# POWER_INPUT.net
KiCad netlist of a schematic drawn in Altium Designer
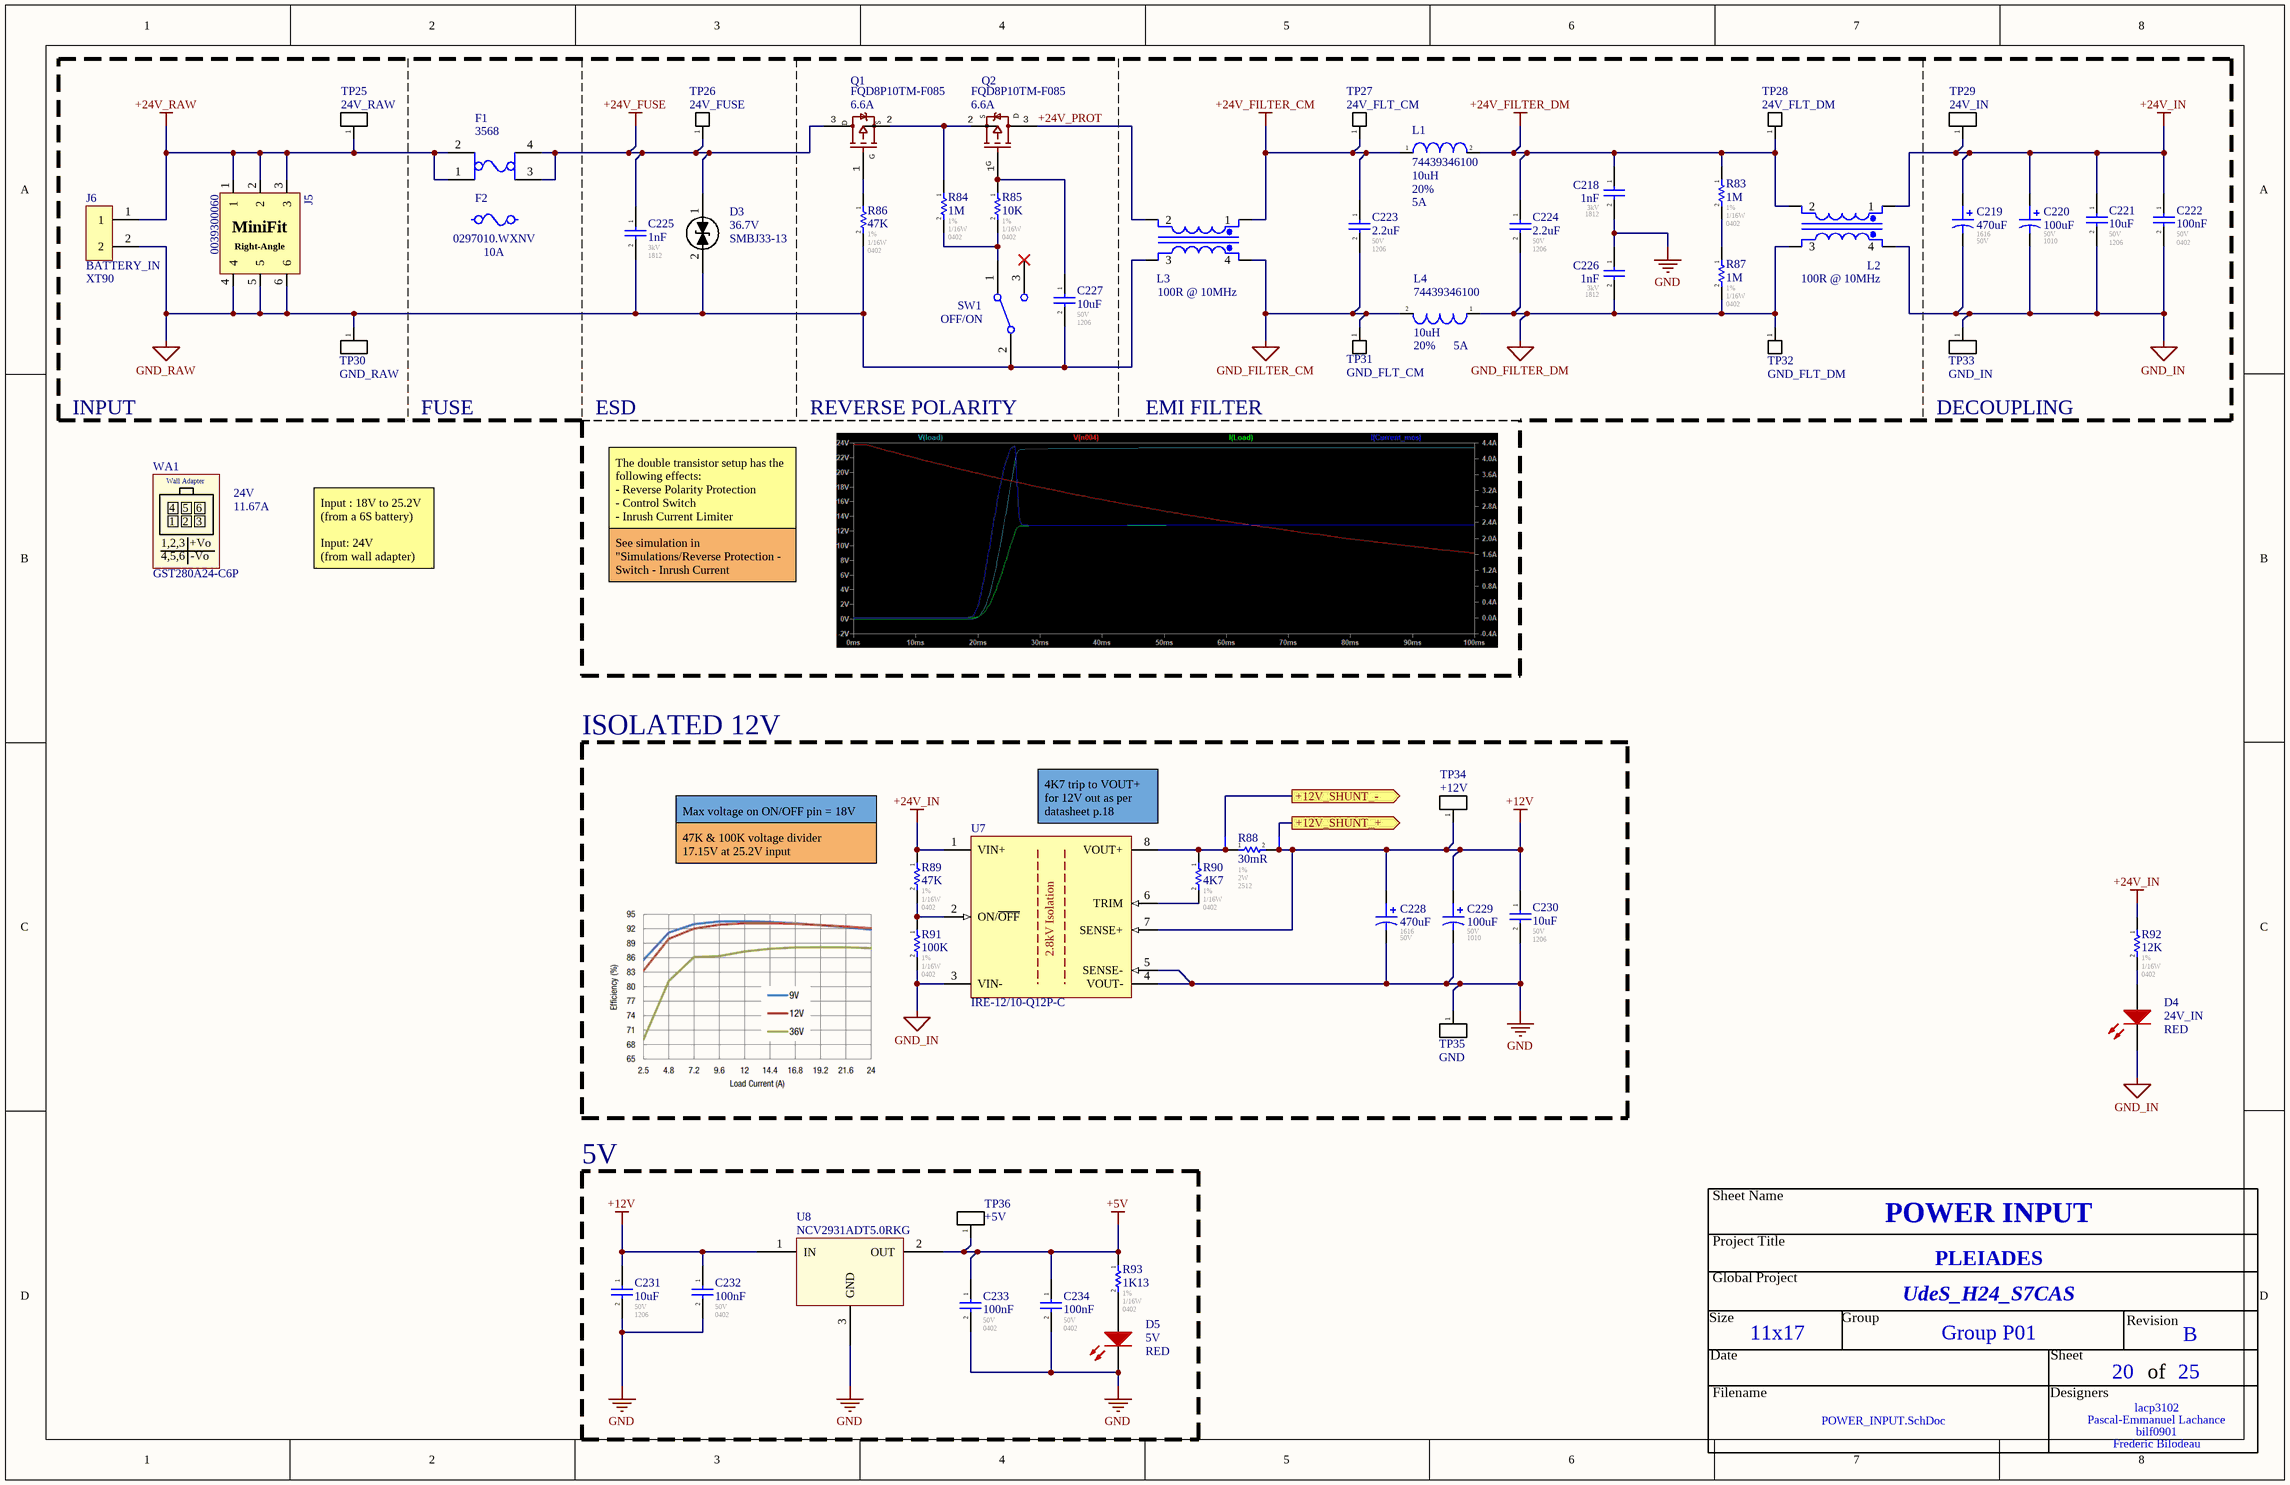
[diagram p0: POWER_INPUT.SchDoc]

(export (version "E")
  (design (tool "Eeschema 10.0.6"))
  (components
    (comp (ref "C218")
      (value "1nF")
      (footprint "1812")
      (description "C1812C102KHRACAUTO\r\n0402 470pF 10% X7R Ceramic Capacitor")
      (fields
        (field (name "MFR") "KEMET")
        (field (name "PART#") "C1812C102KHRACAUTO")
        (field (name "VOLTAGE - RATED") "3kV")
      )
      (libsource (lib "Symbols") (part "CAP_CER"))
    )
    (comp (ref "C219")
      (value "470uF")
      (footprint "CAP_ALU_1616_vishay")
      (description "CAP - ALU 470uF 20% 50V - 1616")
      (fields
        (field (name "MFG") "Vishay Dale")
        (field (name "MFG PART NUMBER") "MAL214699108E3")
        (field (name "VOLTAGE") "50V")
        (field (name "PACKAGE") "1616")
        (field (name "CREATEDBY") "Jonathan Bouchard")
      )
      (libsource (lib "S7CAS_LIB2023") (part "CAP_ALU_MAL214699108E3"))
    )
    (comp (ref "C220")
      (value "100uF")
      (footprint "CAP_ALU_1010_vishay")
      (description "CAP - ALU 100uF 20% 50V - 1010")
      (fields
        (field (name "MFG") "Vishay Dale")
        (field (name "MFG PART NUMBER") "MAL215099101E3")
        (field (name "VOLTAGE") "50V")
        (field (name "PACKAGE") "1010")
        (field (name "CREATEDBY") "Jonathan Bouchard")
      )
      (libsource (lib "S7CAS_LIB2023") (part "CAP_ALU_MAL215099101E3"))
    )
    (comp (ref "C221")
      (value "10uF")
      (footprint "1206")
      (description "GRT31CR61H106KE01L\r\n1206 10uF 10% X5R Ceramic Capacitor")
      (fields
        (field (name "MFR") "Murata")
        (field (name "VOLTAGE - RATED") "50V")
        (field (name "TOLERANCE") "10%")
      )
      (libsource (lib "Symbols") (part "CAP_CER"))
    )
    (comp (ref "C222")
      (value "100nF")
      (footprint "0402")
      (description "GCM155R71H104KE02J\r\n0402 100nF 10% X7R Ceramic Capacitor")
      (fields
        (field (name "MFR") "Murata")
        (field (name "PART#") "GCM155R71H104KE02J")
        (field (name "VOLTAGE - RATED") "50V")
      )
      (libsource (lib "Symbols") (part "CAP_CER"))
    )
    (comp (ref "C223")
      (value "2.2uF")
      (footprint "1206")
      (description "GRT31CR71H225KE13L\r\n1206 2.2uF 10% X7R Ceramic Capacitor")
      (fields
        (field (name "MFR") "Murata")
        (field (name "PART#") "GRT31CR71H225KE13L")
        (field (name "VOLTAGE - RATED") "50V")
      )
      (libsource (lib "Symbols") (part "CAP_CER"))
    )
    (comp (ref "C224")
      (value "2.2uF")
      (footprint "1206")
      (description "GRT31CR71H225KE13L\r\n1206 2.2uF 10% X7R Ceramic Capacitor")
      (fields
        (field (name "MFR") "Murata")
        (field (name "PART#") "GRT31CR71H225KE13L")
        (field (name "VOLTAGE - RATED") "50V")
      )
      (libsource (lib "Symbols") (part "CAP_CER"))
    )
    (comp (ref "C225")
      (value "1nF")
      (footprint "1812")
      (description "C1812C102KHRACAUTO\r\n0402 470pF 10% X7R Ceramic Capacitor")
      (fields
        (field (name "MFR") "KEMET")
        (field (name "PART#") "C1812C102KHRACAUTO")
        (field (name "VOLTAGE - RATED") "3kV")
      )
      (libsource (lib "Symbols") (part "CAP_CER"))
    )
    (comp (ref "C226")
      (value "1nF")
      (footprint "1812")
      (description "C1812C102KHRACAUTO\r\n0402 470pF 10% X7R Ceramic Capacitor")
      (fields
        (field (name "MFR") "KEMET")
        (field (name "PART#") "C1812C102KHRACAUTO")
        (field (name "VOLTAGE - RATED") "3kV")
      )
      (libsource (lib "Symbols") (part "CAP_CER"))
    )
    (comp (ref "C227")
      (value "10uF")
      (footprint "1206")
      (description "GRT31CR61H106KE01L\r\n1206 10uF 10% X5R Ceramic Capacitor")
      (fields
        (field (name "MFR") "Murata")
        (field (name "VOLTAGE - RATED") "50V")
        (field (name "TOLERANCE") "10%")
      )
      (libsource (lib "Symbols") (part "CAP_CER"))
    )
    (comp (ref "C228")
      (value "470uF")
      (footprint "CAP_ALU_1616_vishay")
      (description "CAP - ALU 470uF 20% 50V - 1616")
      (fields
        (field (name "MFG") "Vishay Dale")
        (field (name "MFG PART NUMBER") "MAL214699108E3")
        (field (name "VOLTAGE") "50V")
        (field (name "PACKAGE") "1616")
        (field (name "CREATEDBY") "Jonathan Bouchard")
      )
      (libsource (lib "S7CAS_LIB2023") (part "CAP_ALU_MAL214699108E3"))
    )
    (comp (ref "C229")
      (value "100uF")
      (footprint "CAP_ALU_1010_vishay")
      (description "CAP - ALU 100uF 20% 50V - 1010")
      (fields
        (field (name "MFG") "Vishay Dale")
        (field (name "MFG PART NUMBER") "MAL215099101E3")
        (field (name "VOLTAGE") "50V")
        (field (name "PACKAGE") "1010")
        (field (name "CREATEDBY") "Jonathan Bouchard")
      )
      (libsource (lib "S7CAS_LIB2023") (part "CAP_ALU_MAL215099101E3"))
    )
    (comp (ref "C230")
      (value "10uF")
      (footprint "1206")
      (description "GRT31CR61H106KE01L\r\n1206 10uF 10% X5R Ceramic Capacitor")
      (fields
        (field (name "MFR") "Murata")
        (field (name "VOLTAGE - RATED") "50V")
        (field (name "TOLERANCE") "10%")
      )
      (libsource (lib "Symbols") (part "CAP_CER"))
    )
    (comp (ref "C231")
      (value "10uF")
      (footprint "1206")
      (description "GRT31CR61H106KE01L\r\n1206 10uF 10% X5R Ceramic Capacitor")
      (fields
        (field (name "MFR") "Murata")
        (field (name "VOLTAGE - RATED") "50V")
        (field (name "TOLERANCE") "10%")
      )
      (libsource (lib "Symbols") (part "CAP_CER"))
    )
    (comp (ref "C232")
      (value "100nF")
      (footprint "0402")
      (description "GCM155R71H104KE02J\r\n0402 100nF 10% X7R Ceramic Capacitor")
      (fields
        (field (name "MFR") "Murata")
        (field (name "PART#") "GCM155R71H104KE02J")
        (field (name "VOLTAGE - RATED") "50V")
      )
      (libsource (lib "Symbols") (part "CAP_CER"))
    )
    (comp (ref "C233")
      (value "100nF")
      (footprint "0402")
      (description "GCM155R71H104KE02J\r\n0402 100nF 10% X7R Ceramic Capacitor")
      (fields
        (field (name "MFR") "Murata")
        (field (name "PART#") "GCM155R71H104KE02J")
        (field (name "VOLTAGE - RATED") "50V")
      )
      (libsource (lib "Symbols") (part "CAP_CER"))
    )
    (comp (ref "C234")
      (value "100nF")
      (footprint "0402")
      (description "GCM155R71H104KE02J\r\n0402 100nF 10% X7R Ceramic Capacitor")
      (fields
        (field (name "MFR") "Murata")
        (field (name "PART#") "GCM155R71H104KE02J")
        (field (name "VOLTAGE - RATED") "50V")
      )
      (libsource (lib "Symbols") (part "CAP_CER"))
    )
    (comp (ref "D3")
      (value "SMBJ33-13")
      (footprint "DO214AA (SMB)")
      (description "53.3V Clamp 11.3A Ipp Tvs Diode Surface Mount SMB")
      (fields (field (name "MFR") "SMBJ33CAQ-13-F") (field (name "VOLTAGE - BREAKDOWN") "36.7V"))
      (libsource (lib "Symbols") (part "DIODE_TVS"))
    )
    (comp (ref "D4")
      (value "24V_IN")
      (footprint "LED_0603")
      (description "LED - 620nM RED 2mA - 0603")
      (fields
        (field (name "VOLTAGE") "1.8V")
        (field (name "MFG") "ROHM Semiconductor")
        (field (name "ALTIUM_VALUE") "RED")
        (field (name "CREATEDBY") "Jonathan Bouchard")
      )
      (libsource (lib "S7CAS_LIB2023") (part "LED_SML-311UTT86"))
    )
    (comp (ref "D5")
      (value "5V")
      (footprint "LED_0603")
      (description "LED - 620nM RED 2mA - 0603")
      (fields
        (field (name "VOLTAGE") "1.8V")
        (field (name "MFG") "ROHM Semiconductor")
        (field (name "ALTIUM_VALUE") "RED")
        (field (name "CREATEDBY") "Jonathan Bouchard")
      )
      (libsource (lib "S7CAS_LIB2023") (part "LED_SML-311UTT86"))
    )
    (comp (ref "F1")
      (value "3568")
      (footprint "3568")
      (description "FUSE HOLDER BLADE")
      (fields (field (name "MFR") "Keystone") (field (name "CREATED BY") "Pascal-Emmanuel Lachance"))
      (libsource (lib "CryptLib") (part "FUSE_HOLDER_3568"))
    )
    (comp (ref "F2")
      (value "0297010.WXNV")
      (footprint "0297010.WXNV")
      (description "FUSE AUTO 10A 32V BLADE MINI")
      (fields
        (field (name "MFR") "Littelfuse")
        (field (name "CURRENT - TRIP") "10A")
        (field (name "CREATED BY") "Pascal-Emmanuel Lachance")
      )
      (libsource (lib "CryptLib") (part "FUSE_0297010.WXNV"))
    )
    (comp (ref "J5")
      (value "0039300060")
      (footprint "CON_MINIFIT_0039300060")
      (description "CON - Mini-Fit Through Hole, Right Angle 6 position")
      (fields
        (field (name "CREATEDBY/DATE") "Joel Lemay 2018-06-21")
        (field (name "VERIFIEDBY") "Caroline Paulin - 10 sept 2018")
      )
      (libsource (lib "S7CAS_LIB2023") (part "CON_MINIFIT_0039300060"))
    )
    (comp (ref "J6")
      (value "BATTERY_IN")
      (footprint "XT90")
      (fields (field (name "TYPE") "XT90"))
      (libsource (lib "Connectors") (part "XT90"))
    )
    (comp (ref "L1")
      (value "74439346100")
      (footprint "74439346100")
      (description "Generic Inductor")
      (fields
        (field (name "INDUCTANCE") "10uH")
        (field (name "TOLERANCE") "20%")
        (field (name "CURRENT RATING") "5A")
      )
      (libsource (lib "Symbols") (part "INDUCTOR"))
    )
    (comp (ref "L2")
      (value "100R @ 10MHz")
      (footprint "IND_PLT10HH101150PNL")
      (fields
        (field (name "Comment") "PLT10HH101150PNL")
        (field (name "CREATEDBY/DATE") "Tommy Rossginol - 2019/04/09")
        (field (name "VERIFIEDBY") "Caroline Paulin - 10-04-2019")
      )
      (libsource (lib "S7CAS_LIB2023") (part "IND_PLT10HH101150PNL"))
    )
    (comp (ref "L3")
      (value "100R @ 10MHz")
      (footprint "IND_PLT10HH101150PNL")
      (fields
        (field (name "Comment") "PLT10HH101150PNL")
        (field (name "CREATEDBY/DATE") "Tommy Rossginol - 2019/04/09")
        (field (name "VERIFIEDBY") "Caroline Paulin - 10-04-2019")
      )
      (libsource (lib "S7CAS_LIB2023") (part "IND_PLT10HH101150PNL"))
    )
    (comp (ref "L4")
      (value "74439346100")
      (footprint "74439346100")
      (description "Generic Inductor")
      (fields
        (field (name "INDUCTANCE") "10uH")
        (field (name "TOLERANCE") "20%")
        (field (name "CURRENT RATING") "5A")
      )
      (libsource (lib "Symbols") (part "INDUCTOR"))
    )
    (comp (ref "NT38")
      (value "Net Tie")
      (footprint "NETTIE_5")
      (libsource (lib "Symbols") (part "NET_TIE_SMALL"))
    )
    (comp (ref "NT39")
      (value "Net Tie")
      (footprint "NETTIE_5")
      (libsource (lib "Symbols") (part "NET_TIE_SMALL"))
    )
    (comp (ref "Q1")
      (value "FQD8P10TM-F085")
      (footprint "DPAK")
      (description "P-Channel 100 V 6.6A (Tc) 2.5W (Ta), 44W (Tc) Surface Mount TO-252AA")
      (fields (field (name "MFR") "onsemi") (field (name "CURRENT") "6.6A"))
      (libsource (lib "Symbols") (part "P_CHANNEL"))
    )
    (comp (ref "Q2")
      (value "FQD8P10TM-F085")
      (footprint "DPAK")
      (description "P-Channel 100 V 6.6A (Tc) 2.5W (Ta), 44W (Tc) Surface Mount TO-252AA")
      (fields (field (name "MFR") "onsemi") (field (name "CURRENT") "6.6A"))
      (libsource (lib "Symbols") (part "P_CHANNEL"))
    )
    (comp (ref "R83")
      (value "1M")
      (footprint "RES_0402")
      (description "1M 0402 1% 1/16W Resistor")
      (fields
        (field (name "TOLERANCE") "1%")
        (field (name "POWER") "1/16W")
        (field (name "PACKAGE / CASE") "0402")
      )
      (libsource (lib "Symbols") (part "RESISTOR"))
    )
    (comp (ref "R84")
      (value "1M")
      (footprint "RES_0402")
      (description "1M 0402 1% 1/16W Resistor")
      (fields
        (field (name "TOLERANCE") "1%")
        (field (name "POWER") "1/16W")
        (field (name "PACKAGE / CASE") "0402")
      )
      (libsource (lib "Symbols") (part "RESISTOR"))
    )
    (comp (ref "R85")
      (value "10K")
      (footprint "RES_0402")
      (fields
        (field (name "TOLERANCE") "1%")
        (field (name "POWER") "1/16W")
        (field (name "PACKAGE / CASE") "0402")
      )
      (libsource (lib "Symbols") (part "RESISTOR"))
    )
    (comp (ref "R86")
      (value "47K")
      (footprint "RES_0402")
      (fields
        (field (name "TOLERANCE") "1%")
        (field (name "POWER") "1/16W")
        (field (name "PACKAGE / CASE") "0402")
      )
      (libsource (lib "Symbols") (part "RESISTOR"))
    )
    (comp (ref "R87")
      (value "1M")
      (footprint "RES_0402")
      (description "1M 0402 1% 1/16W Resistor")
      (fields
        (field (name "TOLERANCE") "1%")
        (field (name "POWER") "1/16W")
        (field (name "PACKAGE / CASE") "0402")
      )
      (libsource (lib "Symbols") (part "RESISTOR"))
    )
    (comp (ref "R88")
      (value "30mR")
      (footprint "RES_2512")
      (description "CSRN2512FK30L0")
      (fields
        (field (name "TOLERANCE") "1%")
        (field (name "POWER") "2W")
        (field (name "PACKAGE / CASE") "2512")
      )
      (libsource (lib "Symbols") (part "RESISTOR"))
    )
    (comp (ref "R89")
      (value "47K")
      (footprint "RES_0402")
      (fields
        (field (name "TOLERANCE") "1%")
        (field (name "POWER") "1/16W")
        (field (name "PACKAGE / CASE") "0402")
      )
      (libsource (lib "Symbols") (part "RESISTOR"))
    )
    (comp (ref "R90")
      (value "4K7")
      (footprint "RES_0402")
      (fields
        (field (name "TOLERANCE") "1%")
        (field (name "POWER") "1/16W")
        (field (name "PACKAGE / CASE") "0402")
      )
      (libsource (lib "Symbols") (part "RESISTOR"))
    )
    (comp (ref "R91")
      (value "100K")
      (footprint "RES_0402")
      (fields
        (field (name "TOLERANCE") "1%")
        (field (name "POWER") "1/16W")
        (field (name "PACKAGE / CASE") "0402")
      )
      (libsource (lib "Symbols") (part "RESISTOR"))
    )
    (comp (ref "R92")
      (value "12K")
      (footprint "RES_0402")
      (fields
        (field (name "TOLERANCE") "1%")
        (field (name "POWER") "1/16W")
        (field (name "PACKAGE / CASE") "0402")
      )
      (libsource (lib "Symbols") (part "RESISTOR"))
    )
    (comp (ref "R93")
      (value "1K13")
      (footprint "RES_0402")
      (fields
        (field (name "TOLERANCE") "1%")
        (field (name "POWER") "1/16W")
        (field (name "PACKAGE / CASE") "0402")
      )
      (libsource (lib "Symbols") (part "RESISTOR"))
    )
    (comp (ref "SW1")
      (value "OFF/ON")
      (footprint "1101M2S3CQE2")
      (description "1103M2S3CQE2\r\nSlide Switch SPDT Through Hole")
      (fields (field (name "MFR") "C&K"))
      (libsource (lib "Symbols") (part "SPDT_SWITCH"))
    )
    (comp (ref "TP25")
      (value "24V_RAW")
      (footprint "TP_HOLE")
      (description "Test Point")
      (libsource (lib "Symbols") (part "TESTPOINT"))
    )
    (comp (ref "TP26")
      (value "24V_FUSE")
      (footprint "TP_PAD")
      (description "Test Point")
      (libsource (lib "Symbols") (part "TESTPOINT_PAD"))
    )
    (comp (ref "TP27")
      (value "24V_FLT_CM")
      (footprint "TP_PAD")
      (description "Test Point")
      (libsource (lib "Symbols") (part "TESTPOINT_PAD"))
    )
    (comp (ref "TP28")
      (value "24V_FLT_DM")
      (footprint "TP_PAD")
      (description "Test Point")
      (libsource (lib "Symbols") (part "TESTPOINT_PAD"))
    )
    (comp (ref "TP29")
      (value "24V_IN")
      (footprint "TP_HOLE")
      (description "Test Point")
      (libsource (lib "Symbols") (part "TESTPOINT"))
    )
    (comp (ref "TP30")
      (value "GND_RAW")
      (footprint "TP_HOLE")
      (description "Test Point")
      (libsource (lib "Symbols") (part "TESTPOINT"))
    )
    (comp (ref "TP31")
      (value "GND_FLT_CM")
      (footprint "TP_PAD")
      (description "Test Point")
      (libsource (lib "Symbols") (part "TESTPOINT_PAD"))
    )
    (comp (ref "TP32")
      (value "GND_FLT_DM")
      (footprint "TP_PAD")
      (description "Test Point")
      (libsource (lib "Symbols") (part "TESTPOINT_PAD"))
    )
    (comp (ref "TP33")
      (value "GND_IN")
      (footprint "TP_HOLE")
      (description "Test Point")
      (libsource (lib "Symbols") (part "TESTPOINT"))
    )
    (comp (ref "TP34")
      (value "+12V")
      (footprint "TP_HOLE")
      (description "Test Point")
      (libsource (lib "Symbols") (part "TESTPOINT"))
    )
    (comp (ref "TP35")
      (value "GND")
      (footprint "TP_HOLE")
      (description "Test Point")
      (libsource (lib "Symbols") (part "TESTPOINT"))
    )
    (comp (ref "TP36")
      (value "+5V")
      (footprint "TP_HOLE")
      (description "Test Point")
      (libsource (lib "Symbols") (part "TESTPOINT"))
    )
    (comp (ref "U7")
      (value "IRE-12/10-Q12P-C")
      (footprint "IRE-Q12")
      (description "Isolated DC/DC Converters - Through Hole 9V-36VIN 24VOUT 120W")
      (fields (field (name "MFR") "Murata"))
      (libsource (lib "Misc") (part "IRE-24/5-Q12P-C"))
    )
    (comp (ref "U8")
      (value "NCV2931ADT5.0RKG")
      (footprint "DPAK")
      (libsource (lib "Misc") (part "NCV2931ADT5.0RKG"))
    )
    (comp (ref "WA1")
      (value "GST280A24-C6P")
      (footprint "Model Name")
      (description "UND - AC/DC DESKTOP ADAPTER 24V 280W - MEC")
      (fields
        (field (name "TOLERANCE") "±3%")
        (field (name "CURRENT RATING") "11.67A")
        (field (name "ALTIUM_VALUE") "24V")
        (field (name "CREATEDBY/DATE") "Caroline Paulin - 5 avril 2019")
        (field (name "VERIFIEDBY") "Nicolas V. (2019-07-05)")
      )
      (libsource (lib "S7CAS_LIB2023") (part "UND_GST280A24-C6P"))
    )
  )
  (nets
    (net (code "1") (name "+5V") (class "Default")
      (node (ref "C233") (pin "1") (pinfunction "1_1") (pintype "passive"))
      (node (ref "C234") (pin "1") (pinfunction "1_1") (pintype "passive"))
      (node (ref "R93") (pin "1") (pinfunction "1_1") (pintype "passive"))
      (node (ref "TP36") (pin "1") (pinfunction "A_1") (pintype "passive"))
      (node (ref "U8") (pin "2") (pinfunction "OUT_2") (pintype "passive"))
    )
    (net (code "2") (name "+12V") (class "Default")
      (node (ref "C228") (pin "1") (pinfunction "1_1") (pintype "passive"))
      (node (ref "C229") (pin "1") (pinfunction "1_1") (pintype "passive"))
      (node (ref "C230") (pin "1") (pinfunction "1_1") (pintype "passive"))
      (node (ref "C231") (pin "1") (pinfunction "1_1") (pintype "passive"))
      (node (ref "C232") (pin "1") (pinfunction "1_1") (pintype "passive"))
      (node (ref "NT39") (pin "1") (pinfunction "1_1") (pintype "passive"))
      (node (ref "R88") (pin "2") (pinfunction "2_2") (pintype "passive"))
      (node (ref "TP34") (pin "1") (pinfunction "A_1") (pintype "passive"))
      (node (ref "U7") (pin "7") (pinfunction "SENSE+_7") (pintype "input"))
      (node (ref "U8") (pin "1") (pinfunction "IN_1") (pintype "passive"))
    )
    (net (code "3") (name "+24V_FILTER_CM") (class "Default")
      (node (ref "C223") (pin "1") (pinfunction "1_1") (pintype "passive"))
      (node (ref "L1") (pin "1") (pinfunction "1_1") (pintype "passive"))
      (node (ref "L3") (pin "1") (pinfunction "1_1") (pintype "passive"))
      (node (ref "TP27") (pin "1") (pinfunction "A_1") (pintype "passive"))
    )
    (net (code "4") (name "+24V_FILTER_DM") (class "Default")
      (node (ref "C218") (pin "1") (pinfunction "1_1") (pintype "passive"))
      (node (ref "C224") (pin "1") (pinfunction "1_1") (pintype "passive"))
      (node (ref "L1") (pin "2") (pinfunction "2_2") (pintype "passive"))
      (node (ref "L2") (pin "2") (pinfunction "2_2") (pintype "passive"))
      (node (ref "R83") (pin "1") (pinfunction "1_1") (pintype "passive"))
      (node (ref "TP28") (pin "1") (pinfunction "A_1") (pintype "passive"))
    )
    (net (code "5") (name "+24V_FUSE") (class "Default")
      (node (ref "C225") (pin "1") (pinfunction "1_1") (pintype "passive"))
      (node (ref "D3") (pin "1") (pinfunction "A_1") (pintype "passive"))
      (node (ref "F1") (pin "3") (pinfunction "3_3") (pintype "passive"))
      (node (ref "F1") (pin "4") (pinfunction "4_4") (pintype "passive"))
      (node (ref "Q1") (pin "3") (pintype "passive"))
      (node (ref "TP26") (pin "1") (pinfunction "A_1") (pintype "passive"))
    )
    (net (code "6") (name "+24V_IN") (class "Default")
      (node (ref "C219") (pin "1") (pinfunction "1_1") (pintype "passive"))
      (node (ref "C220") (pin "1") (pinfunction "1_1") (pintype "passive"))
      (node (ref "C221") (pin "1") (pinfunction "1_1") (pintype "passive"))
      (node (ref "C222") (pin "1") (pinfunction "1_1") (pintype "passive"))
      (node (ref "L2") (pin "1") (pinfunction "1_1") (pintype "passive"))
      (node (ref "R89") (pin "1") (pinfunction "1_1") (pintype "passive"))
      (node (ref "R92") (pin "1") (pinfunction "1_1") (pintype "passive"))
      (node (ref "TP29") (pin "1") (pinfunction "A_1") (pintype "passive"))
      (node (ref "U7") (pin "1") (pinfunction "VIN+_1") (pintype "power_in"))
    )
    (net (code "7") (name "+24V_RAW") (class "Default")
      (node (ref "F1") (pin "1") (pinfunction "1_1") (pintype "passive"))
      (node (ref "F1") (pin "2") (pinfunction "2_2") (pintype "passive"))
      (node (ref "J5") (pin "1") (pinfunction "1_1") (pintype "passive"))
      (node (ref "J5") (pin "2") (pinfunction "2_2") (pintype "passive"))
      (node (ref "J5") (pin "3") (pinfunction "3_3") (pintype "passive"))
      (node (ref "J6") (pin "1") (pinfunction "1_1") (pintype "passive"))
      (node (ref "TP25") (pin "1") (pinfunction "A_1") (pintype "passive"))
    )
    (net (code "8") (name "/+12V_SHUNT_+") (class "Default")
      (node (ref "NT39") (pin "2") (pinfunction "2_2") (pintype "passive"))
    )
    (net (code "9") (name "/+12V_SHUNT_-") (class "Default")
      (node (ref "NT38") (pin "2") (pinfunction "2_2") (pintype "passive"))
    )
    (net (code "10") (name "/+24V_PROT") (class "Default")
      (node (ref "L3") (pin "2") (pinfunction "2_2") (pintype "passive"))
      (node (ref "Q2") (pin "3") (pintype "passive"))
    )
    (net (code "11") (name "GND") (class "Default")
      (node (ref "C218") (pin "2") (pinfunction "2_2") (pintype "passive"))
      (node (ref "C226") (pin "1") (pinfunction "1_1") (pintype "passive"))
      (node (ref "C228") (pin "2") (pinfunction "2_2") (pintype "passive"))
      (node (ref "C229") (pin "2") (pinfunction "2_2") (pintype "passive"))
      (node (ref "C230") (pin "2") (pinfunction "2_2") (pintype "passive"))
      (node (ref "C231") (pin "2") (pinfunction "2_2") (pintype "passive"))
      (node (ref "C232") (pin "2") (pinfunction "2_2") (pintype "passive"))
      (node (ref "C233") (pin "2") (pinfunction "2_2") (pintype "passive"))
      (node (ref "C234") (pin "2") (pinfunction "2_2") (pintype "passive"))
      (node (ref "D5") (pin "2") (pinfunction "K_2") (pintype "passive"))
      (node (ref "TP35") (pin "1") (pinfunction "A_1") (pintype "passive"))
      (node (ref "U7") (pin "4") (pinfunction "VOUT-_4") (pintype "power_in"))
      (node (ref "U7") (pin "5") (pinfunction "SENSE-_5") (pintype "input"))
      (node (ref "U8") (pin "3") (pinfunction "GND_3") (pintype "passive"))
    )
    (net (code "12") (name "GND_FILTER_CM") (class "Default")
      (node (ref "C223") (pin "2") (pinfunction "2_2") (pintype "passive"))
      (node (ref "L3") (pin "4") (pinfunction "4_4") (pintype "passive"))
      (node (ref "L4") (pin "2") (pinfunction "2_2") (pintype "passive"))
      (node (ref "TP31") (pin "1") (pinfunction "A_1") (pintype "passive"))
    )
    (net (code "13") (name "GND_FILTER_DM") (class "Default")
      (node (ref "C224") (pin "2") (pinfunction "2_2") (pintype "passive"))
      (node (ref "C226") (pin "2") (pinfunction "2_2") (pintype "passive"))
      (node (ref "L2") (pin "3") (pinfunction "3_3") (pintype "passive"))
      (node (ref "L4") (pin "1") (pinfunction "1_1") (pintype "passive"))
      (node (ref "R87") (pin "2") (pinfunction "2_2") (pintype "passive"))
      (node (ref "TP32") (pin "1") (pinfunction "A_1") (pintype "passive"))
    )
    (net (code "14") (name "GND_IN") (class "Default")
      (node (ref "C219") (pin "2") (pinfunction "2_2") (pintype "passive"))
      (node (ref "C220") (pin "2") (pinfunction "2_2") (pintype "passive"))
      (node (ref "C221") (pin "2") (pinfunction "2_2") (pintype "passive"))
      (node (ref "C222") (pin "2") (pinfunction "2_2") (pintype "passive"))
      (node (ref "D4") (pin "2") (pinfunction "K_2") (pintype "passive"))
      (node (ref "L2") (pin "4") (pinfunction "4_4") (pintype "passive"))
      (node (ref "R91") (pin "2") (pinfunction "2_2") (pintype "passive"))
      (node (ref "TP33") (pin "1") (pinfunction "A_1") (pintype "passive"))
      (node (ref "U7") (pin "3") (pinfunction "VIN-_3") (pintype "power_in"))
    )
    (net (code "15") (name "GND_RAW") (class "Default")
      (node (ref "C225") (pin "2") (pinfunction "2_2") (pintype "passive"))
      (node (ref "C227") (pin "2") (pinfunction "2_2") (pintype "passive"))
      (node (ref "D3") (pin "2") (pinfunction "C_2") (pintype "passive"))
      (node (ref "J5") (pin "4") (pinfunction "4_4") (pintype "passive"))
      (node (ref "J5") (pin "5") (pinfunction "5_5") (pintype "passive"))
      (node (ref "J5") (pin "6") (pinfunction "6_6") (pintype "passive"))
      (node (ref "J6") (pin "2") (pinfunction "2_2") (pintype "passive"))
      (node (ref "L3") (pin "3") (pinfunction "3_3") (pintype "passive"))
      (node (ref "R86") (pin "2") (pinfunction "2_2") (pintype "passive"))
      (node (ref "SW1") (pin "2") (pinfunction "P_2") (pintype "passive"))
      (node (ref "TP30") (pin "1") (pinfunction "A_1") (pintype "passive"))
    )
    (net (code "16") (name "Net-(C227-Pad1)") (class "Default")
      (node (ref "C227") (pin "1") (pinfunction "1_1") (pintype "passive"))
      (node (ref "Q2") (pin "1") (pintype "passive"))
      (node (ref "R85") (pin "1") (pinfunction "1_1") (pintype "passive"))
    )
    (net (code "17") (name "Net-(D4-A)") (class "Default")
      (node (ref "D4") (pin "1") (pinfunction "A_1") (pintype "passive"))
      (node (ref "R92") (pin "2") (pinfunction "2_2") (pintype "passive"))
    )
    (net (code "18") (name "Net-(D5-A)") (class "Default")
      (node (ref "D5") (pin "1") (pinfunction "A_1") (pintype "passive"))
      (node (ref "R93") (pin "2") (pinfunction "2_2") (pintype "passive"))
    )
    (net (code "19") (name "Net-(Q1-Pad1)") (class "Default")
      (node (ref "Q1") (pin "1") (pintype "passive"))
      (node (ref "R86") (pin "1") (pinfunction "1_1") (pintype "passive"))
    )
    (net (code "20") (name "Net-(Q1-Pad2)") (class "Default")
      (node (ref "Q1") (pin "2") (pintype "passive"))
      (node (ref "Q2") (pin "2") (pintype "passive"))
      (node (ref "R84") (pin "1") (pinfunction "1_1") (pintype "passive"))
    )
    (net (code "21") (name "Net-(R83-Pad2)") (class "Default")
      (node (ref "R83") (pin "2") (pinfunction "2_2") (pintype "passive"))
      (node (ref "R87") (pin "1") (pinfunction "1_1") (pintype "passive"))
    )
    (net (code "22") (name "Net-(SW1-A)") (class "Default")
      (node (ref "R84") (pin "2") (pinfunction "2_2") (pintype "passive"))
      (node (ref "R85") (pin "2") (pinfunction "2_2") (pintype "passive"))
      (node (ref "SW1") (pin "1") (pinfunction "A_1") (pintype "passive"))
    )
    (net (code "23") (name "Net-(U7-ON{slash}~{OFF})") (class "Default")
      (node (ref "R89") (pin "2") (pinfunction "2_2") (pintype "passive"))
      (node (ref "R91") (pin "1") (pinfunction "1_1") (pintype "passive"))
      (node (ref "U7") (pin "2") (pinfunction "ON/~{OFF}_2") (pintype "input"))
    )
    (net (code "24") (name "Net-(U7-TRIM)") (class "Default")
      (node (ref "R90") (pin "2") (pinfunction "2_2") (pintype "passive"))
      (node (ref "U7") (pin "6") (pinfunction "TRIM_6") (pintype "input"))
    )
    (net (code "25") (name "Net-(U7-VOUT+)") (class "Default")
      (node (ref "NT38") (pin "1") (pinfunction "1_1") (pintype "passive"))
      (node (ref "R88") (pin "1") (pinfunction "1_1") (pintype "passive"))
      (node (ref "R90") (pin "1") (pinfunction "1_1") (pintype "passive"))
      (node (ref "U7") (pin "8") (pinfunction "VOUT+_8") (pintype "power_in"))
    )
    (net (code "26") (name "unconnected-(SW1-B-Pad3)") (class "Default")
      (node (ref "SW1") (pin "3") (pinfunction "B_3") (pintype "passive+no_connect"))
    )
  )
)
